# RPIBoard.net
KiCad netlist of a schematic drawn in EAGLE
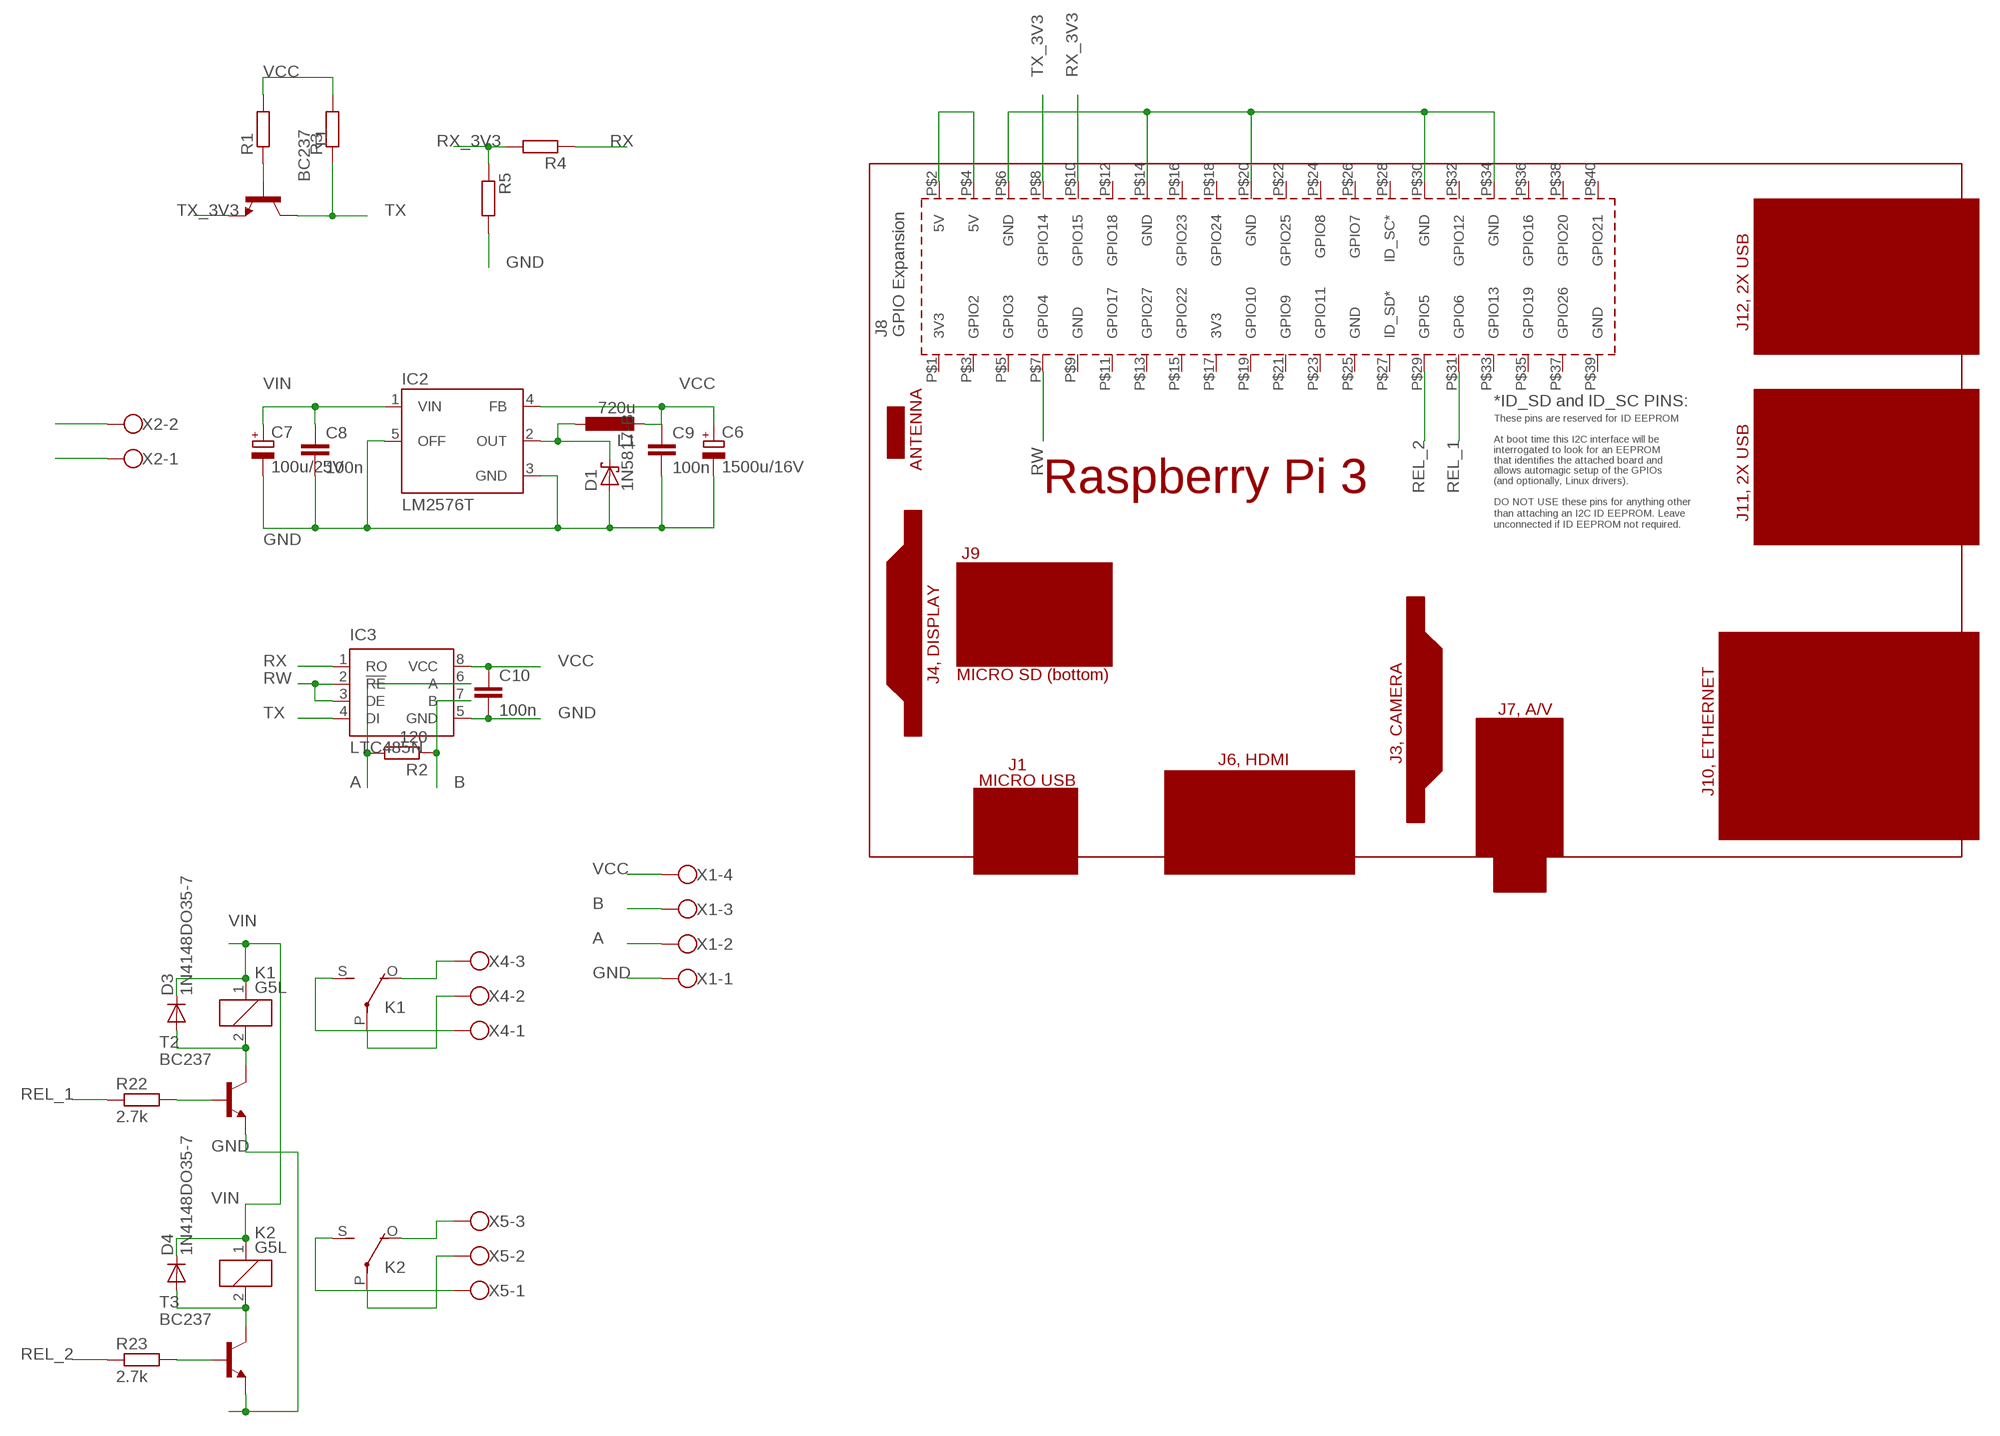
[diagram p0: schematic, sheet 1]

(export (version "E")
  (design (tool "Eeschema 10.0.6"))
  (components
    (comp (ref "C6")
      (value "1500u/16V")
      (footprint "eagle-import:E5-10,5")
      (libsource (lib "eagle-import") (part "CPOL-EUE5-10.5"))
    )
    (comp (ref "C7")
      (value "100u/25V")
      (footprint "eagle-import:E2,5-7")
      (libsource (lib "eagle-import") (part "CPOL-EUE2.5-7"))
    )
    (comp (ref "C8")
      (value "100n")
      (footprint "eagle-import:C025-024X044")
      (libsource (lib "eagle-import") (part "C-EU025-024X044"))
    )
    (comp (ref "C9")
      (value "100n")
      (footprint "eagle-import:C025-024X044")
      (libsource (lib "eagle-import") (part "C-EU025-024X044"))
    )
    (comp (ref "C10")
      (value "100n")
      (footprint "eagle-import:C025-024X044")
      (libsource (lib "eagle-import") (part "C-EU025-024X044"))
    )
    (comp (ref "D1")
      (value "1N5817-B")
      (footprint "eagle-import:DO41-7.6")
      (libsource (lib "eagle-import") (part "1N5817-B"))
    )
    (comp (ref "D3")
      (value "1N4148DO35-7")
      (footprint "eagle-import:DO35-7")
      (libsource (lib "eagle-import") (part "1N4148DO35-7"))
    )
    (comp (ref "D4")
      (value "1N4148DO35-7")
      (footprint "eagle-import:DO35-7")
      (libsource (lib "eagle-import") (part "1N4148DO35-7"))
    )
    (comp (ref "IC2")
      (value "LM2576T")
      (footprint "eagle-import:TO220-5")
      (libsource (lib "eagle-import") (part "LM2576T"))
    )
    (comp (ref "IC3")
      (value "LTC485N")
      (footprint "eagle-import:DIL08")
      (libsource (lib "eagle-import") (part "LTC485N"))
    )
    (comp (ref "K1")
      (value "G5L")
      (footprint "eagle-import:G5LE")
      (libsource (lib "eagle-import") (part "G5L"))
    )
    (comp (ref "K2")
      (value "G5L")
      (footprint "eagle-import:G5LE")
      (libsource (lib "eagle-import") (part "G5L"))
    )
    (comp (ref "L1")
      (value "720u")
      (footprint "eagle-import:TJ3-U1")
      (libsource (lib "eagle-import") (part "L-EUTJ3-U1"))
    )
    (comp (ref "PCB1")
      (value "RPI3")
      (footprint "eagle-import:RPI3")
      (libsource (lib "eagle-import") (part "RPI3"))
    )
    (comp (ref "R1")
      (value "R-EU_0207/7")
      (footprint "eagle-import:0207_7")
      (libsource (lib "eagle-import") (part "R-EU_0207/7"))
    )
    (comp (ref "R2")
      (value "120")
      (footprint "eagle-import:0204_7")
      (libsource (lib "eagle-import") (part "R-EU_0204/7"))
    )
    (comp (ref "R3")
      (value "R-EU_0207/7")
      (footprint "eagle-import:0207_7")
      (libsource (lib "eagle-import") (part "R-EU_0207/7"))
    )
    (comp (ref "R4")
      (value "R-EU_0207/7")
      (footprint "eagle-import:0207_7")
      (libsource (lib "eagle-import") (part "R-EU_0207/7"))
    )
    (comp (ref "R5")
      (value "R-EU_0207/7")
      (footprint "eagle-import:0207_7")
      (libsource (lib "eagle-import") (part "R-EU_0207/7"))
    )
    (comp (ref "R22")
      (value "2.7k")
      (footprint "eagle-import:0204_7")
      (libsource (lib "eagle-import") (part "R-EU_0204/7"))
    )
    (comp (ref "R23")
      (value "2.7k")
      (footprint "eagle-import:0204_7")
      (libsource (lib "eagle-import") (part "R-EU_0204/7"))
    )
    (comp (ref "T1")
      (value "BC237")
      (footprint "eagle-import:TO92")
      (libsource (lib "eagle-import") (part "BC237"))
    )
    (comp (ref "T2")
      (value "BC237")
      (footprint "eagle-import:TO92")
      (libsource (lib "eagle-import") (part "BC237"))
    )
    (comp (ref "T3")
      (value "BC237")
      (footprint "eagle-import:TO92")
      (libsource (lib "eagle-import") (part "BC237"))
    )
    (comp (ref "X1")
      (value "W237-4")
      (footprint "eagle-import:W237-4")
      (libsource (lib "eagle-import") (part "W237-4"))
    )
    (comp (ref "X2")
      (value "W237-102")
      (footprint "eagle-import:W237-102")
      (fields (field (name "MPN") "237-102"))
      (libsource (lib "eagle-import") (part "W237-102"))
    )
    (comp (ref "X4")
      (value "W237-103")
      (footprint "eagle-import:W237-103")
      (fields (field (name "MPN") "237-103"))
      (libsource (lib "eagle-import") (part "W237-103"))
    )
    (comp (ref "X5")
      (value "W237-103")
      (footprint "eagle-import:W237-103")
      (fields (field (name "MPN") "237-103"))
      (libsource (lib "eagle-import") (part "W237-103"))
    )
  )
  (nets
    (net (code "1") (name "/A") (class "Default")
      (node (ref "IC3") (pin "6") (pinfunction "A_6") (pintype "bidirectional"))
      (node (ref "R2") (pin "2") (pinfunction "2_2") (pintype "passive"))
      (node (ref "X1") (pin "2") (pinfunction "KL_2") (pintype "passive"))
    )
    (net (code "2") (name "/B") (class "Default")
      (node (ref "IC3") (pin "7") (pinfunction "B_7") (pintype "bidirectional"))
      (node (ref "R2") (pin "1") (pinfunction "1_1") (pintype "passive"))
      (node (ref "X1") (pin "3") (pinfunction "KL_3") (pintype "passive"))
    )
    (net (code "3") (name "/GND") (class "Default")
      (node (ref "C10") (pin "2") (pinfunction "2_2") (pintype "passive"))
      (node (ref "C6") (pin "-") (pinfunction "-_-") (pintype "passive"))
      (node (ref "C7") (pin "-") (pinfunction "-_-") (pintype "passive"))
      (node (ref "C8") (pin "2") (pinfunction "2_2") (pintype "passive"))
      (node (ref "C9") (pin "2") (pinfunction "2_2") (pintype "passive"))
      (node (ref "D1") (pin "A") (pinfunction "A_A") (pintype "passive"))
      (node (ref "IC2") (pin "3") (pinfunction "GND_3") (pintype "power_in"))
      (node (ref "IC2") (pin "5") (pinfunction "OFF_5") (pintype "input"))
      (node (ref "IC3") (pin "5") (pinfunction "GND_5") (pintype "input"))
      (node (ref "PCB1") (pin "P$14") (pinfunction "GND_P$14") (pintype "bidirectional"))
      (node (ref "PCB1") (pin "P$20") (pinfunction "GND_P$20") (pintype "bidirectional"))
      (node (ref "PCB1") (pin "P$30") (pinfunction "GND_P$30") (pintype "bidirectional"))
      (node (ref "PCB1") (pin "P$34") (pinfunction "GND_P$34") (pintype "bidirectional"))
      (node (ref "PCB1") (pin "P$6") (pinfunction "GND_P$6") (pintype "bidirectional"))
      (node (ref "R5") (pin "2") (pinfunction "2_2") (pintype "passive"))
      (node (ref "T2") (pin "1") (pinfunction "E_1") (pintype "passive"))
      (node (ref "T3") (pin "1") (pinfunction "E_1") (pintype "passive"))
      (node (ref "X1") (pin "1") (pinfunction "KL_1") (pintype "passive"))
      (node (ref "X2") (pin "1") (pinfunction "KL_1") (pintype "passive"))
    )
    (net (code "4") (name "/REL_1") (class "Default")
      (node (ref "PCB1") (pin "P$31") (pinfunction "GPIO6_P$31") (pintype "bidirectional"))
      (node (ref "R22") (pin "1") (pinfunction "1_1") (pintype "passive"))
    )
    (net (code "5") (name "/REL_2") (class "Default")
      (node (ref "PCB1") (pin "P$29") (pinfunction "GPIO5_P$29") (pintype "bidirectional"))
      (node (ref "R23") (pin "1") (pinfunction "1_1") (pintype "passive"))
    )
    (net (code "6") (name "/RW") (class "Default")
      (node (ref "IC3") (pin "2") (pinfunction "~{RE}_2") (pintype "input"))
      (node (ref "IC3") (pin "3") (pinfunction "DE_3") (pintype "input"))
      (node (ref "PCB1") (pin "P$7") (pinfunction "GPIO4_P$7") (pintype "bidirectional"))
    )
    (net (code "7") (name "/RX") (class "Default")
      (node (ref "IC3") (pin "1") (pinfunction "RO_1") (pintype "output"))
      (node (ref "R4") (pin "1") (pinfunction "1_1") (pintype "passive"))
    )
    (net (code "8") (name "/RX_3V3") (class "Default")
      (node (ref "PCB1") (pin "P$10") (pinfunction "GPIO15_P$10") (pintype "bidirectional"))
      (node (ref "R4") (pin "2") (pinfunction "2_2") (pintype "passive"))
      (node (ref "R5") (pin "1") (pinfunction "1_1") (pintype "passive"))
    )
    (net (code "9") (name "/TX") (class "Default")
      (node (ref "IC3") (pin "4") (pinfunction "DI_4") (pintype "input"))
      (node (ref "R3") (pin "1") (pinfunction "1_1") (pintype "passive"))
      (node (ref "T1") (pin "3") (pinfunction "C_3") (pintype "passive"))
    )
    (net (code "10") (name "/TX_3V3") (class "Default")
      (node (ref "PCB1") (pin "P$8") (pinfunction "GPIO14_P$8") (pintype "bidirectional"))
      (node (ref "T1") (pin "1") (pinfunction "E_1") (pintype "passive"))
    )
    (net (code "11") (name "/VCC") (class "Default")
      (node (ref "C10") (pin "1") (pinfunction "1_1") (pintype "passive"))
      (node (ref "C6") (pin "+") (pinfunction "+_+") (pintype "passive"))
      (node (ref "C9") (pin "1") (pinfunction "1_1") (pintype "passive"))
      (node (ref "IC2") (pin "4") (pinfunction "FB_4") (pintype "input"))
      (node (ref "IC3") (pin "8") (pinfunction "VCC_8") (pintype "input"))
      (node (ref "L1") (pin "2") (pinfunction "2_2") (pintype "passive"))
      (node (ref "PCB1") (pin "P$2") (pinfunction "5V_P$2") (pintype "bidirectional"))
      (node (ref "PCB1") (pin "P$4") (pinfunction "5V_P$4") (pintype "bidirectional"))
      (node (ref "R1") (pin "2") (pinfunction "2_2") (pintype "passive"))
      (node (ref "R3") (pin "2") (pinfunction "2_2") (pintype "passive"))
      (node (ref "X1") (pin "4") (pinfunction "KL_4") (pintype "passive"))
    )
    (net (code "12") (name "/VIN") (class "Default")
      (node (ref "C7") (pin "+") (pinfunction "+_+") (pintype "passive"))
      (node (ref "C8") (pin "1") (pinfunction "1_1") (pintype "passive"))
      (node (ref "D3") (pin "C") (pinfunction "C_C") (pintype "passive"))
      (node (ref "D4") (pin "C") (pinfunction "C_C") (pintype "passive"))
      (node (ref "IC2") (pin "1") (pinfunction "VIN_1") (pintype "power_in"))
      (node (ref "K1") (pin "1") (pinfunction "1_1") (pintype "passive"))
      (node (ref "K2") (pin "1") (pinfunction "1_1") (pintype "passive"))
      (node (ref "X2") (pin "2") (pinfunction "KL_2") (pintype "passive"))
    )
    (net (code "13") (name "Net-(IC2-OUT)") (class "Default")
      (node (ref "D1") (pin "C") (pinfunction "C_C") (pintype "passive"))
      (node (ref "IC2") (pin "2") (pinfunction "OUT_2") (pintype "output"))
      (node (ref "L1") (pin "1") (pinfunction "1_1") (pintype "passive"))
    )
    (net (code "14") (name "Net-(T1-B)") (class "Default")
      (node (ref "R1") (pin "1") (pinfunction "1_1") (pintype "passive"))
      (node (ref "T1") (pin "2") (pinfunction "B_2") (pintype "passive"))
    )
    (net (code "15") (name "Net-(T2-B)") (class "Default")
      (node (ref "R22") (pin "2") (pinfunction "2_2") (pintype "passive"))
      (node (ref "T2") (pin "2") (pinfunction "B_2") (pintype "passive"))
    )
    (net (code "16") (name "Net-(T2-C)") (class "Default")
      (node (ref "D3") (pin "A") (pinfunction "A_A") (pintype "passive"))
      (node (ref "K1") (pin "2") (pinfunction "2_2") (pintype "passive"))
      (node (ref "T2") (pin "3") (pinfunction "C_3") (pintype "passive"))
    )
    (net (code "17") (name "Net-(T3-B)") (class "Default")
      (node (ref "R23") (pin "2") (pinfunction "2_2") (pintype "passive"))
      (node (ref "T3") (pin "2") (pinfunction "B_2") (pintype "passive"))
    )
    (net (code "18") (name "Net-(T3-C)") (class "Default")
      (node (ref "D4") (pin "A") (pinfunction "A_A") (pintype "passive"))
      (node (ref "K2") (pin "2") (pinfunction "2_2") (pintype "passive"))
      (node (ref "T3") (pin "3") (pinfunction "C_3") (pintype "passive"))
    )
    (net (code "19") (name "Net-(X4A-KL)") (class "Default")
      (node (ref "K1") (pin "S") (pinfunction "S_S") (pintype "passive"))
      (node (ref "X4") (pin "1") (pinfunction "KL_1") (pintype "passive"))
    )
    (net (code "20") (name "Net-(X4B-KL)") (class "Default")
      (node (ref "K1") (pin "P") (pinfunction "P_P") (pintype "passive"))
      (node (ref "X4") (pin "2") (pinfunction "KL_2") (pintype "passive"))
    )
    (net (code "21") (name "Net-(X4C-KL)") (class "Default")
      (node (ref "K1") (pin "O") (pinfunction "O_O") (pintype "passive"))
      (node (ref "X4") (pin "3") (pinfunction "KL_3") (pintype "passive"))
    )
    (net (code "22") (name "Net-(X5A-KL)") (class "Default")
      (node (ref "K2") (pin "S") (pinfunction "S_S") (pintype "passive"))
      (node (ref "X5") (pin "1") (pinfunction "KL_1") (pintype "passive"))
    )
    (net (code "23") (name "Net-(X5B-KL)") (class "Default")
      (node (ref "K2") (pin "P") (pinfunction "P_P") (pintype "passive"))
      (node (ref "X5") (pin "2") (pinfunction "KL_2") (pintype "passive"))
    )
    (net (code "24") (name "Net-(X5C-KL)") (class "Default")
      (node (ref "K2") (pin "O") (pinfunction "O_O") (pintype "passive"))
      (node (ref "X5") (pin "3") (pinfunction "KL_3") (pintype "passive"))
    )
    (net (code "25") (name "unconnected-(PCB1-3V3-PadP$1)") (class "Default")
      (node (ref "PCB1") (pin "P$1") (pinfunction "3V3_P$1") (pintype "bidirectional"))
    )
    (net (code "26") (name "unconnected-(PCB1-3V3-PadP$17)") (class "Default")
      (node (ref "PCB1") (pin "P$17") (pinfunction "3V3_P$17") (pintype "bidirectional"))
    )
    (net (code "27") (name "unconnected-(PCB1-GND-PadP$9)") (class "Default")
      (node (ref "PCB1") (pin "P$9") (pinfunction "GND_P$9") (pintype "bidirectional"))
    )
    (net (code "28") (name "unconnected-(PCB1-GND-PadP$25)") (class "Default")
      (node (ref "PCB1") (pin "P$25") (pinfunction "GND_P$25") (pintype "bidirectional"))
    )
    (net (code "29") (name "unconnected-(PCB1-GND-PadP$39)") (class "Default")
      (node (ref "PCB1") (pin "P$39") (pinfunction "GND_P$39") (pintype "bidirectional"))
    )
    (net (code "30") (name "unconnected-(PCB1-GPIO2-PadP$3)") (class "Default")
      (node (ref "PCB1") (pin "P$3") (pinfunction "GPIO2_P$3") (pintype "bidirectional"))
    )
    (net (code "31") (name "unconnected-(PCB1-GPIO3-PadP$5)") (class "Default")
      (node (ref "PCB1") (pin "P$5") (pinfunction "GPIO3_P$5") (pintype "bidirectional"))
    )
    (net (code "32") (name "unconnected-(PCB1-GPIO7-PadP$26)") (class "Default")
      (node (ref "PCB1") (pin "P$26") (pinfunction "GPIO7_P$26") (pintype "bidirectional"))
    )
    (net (code "33") (name "unconnected-(PCB1-GPIO8-PadP$24)") (class "Default")
      (node (ref "PCB1") (pin "P$24") (pinfunction "GPIO8_P$24") (pintype "bidirectional"))
    )
    (net (code "34") (name "unconnected-(PCB1-GPIO9-PadP$21)") (class "Default")
      (node (ref "PCB1") (pin "P$21") (pinfunction "GPIO9_P$21") (pintype "bidirectional"))
    )
    (net (code "35") (name "unconnected-(PCB1-GPIO10-PadP$19)") (class "Default")
      (node (ref "PCB1") (pin "P$19") (pinfunction "GPIO10_P$19") (pintype "bidirectional"))
    )
    (net (code "36") (name "unconnected-(PCB1-GPIO11-PadP$23)") (class "Default")
      (node (ref "PCB1") (pin "P$23") (pinfunction "GPIO11_P$23") (pintype "bidirectional"))
    )
    (net (code "37") (name "unconnected-(PCB1-GPIO12-PadP$32)") (class "Default")
      (node (ref "PCB1") (pin "P$32") (pinfunction "GPIO12_P$32") (pintype "bidirectional"))
    )
    (net (code "38") (name "unconnected-(PCB1-GPIO13-PadP$33)") (class "Default")
      (node (ref "PCB1") (pin "P$33") (pinfunction "GPIO13_P$33") (pintype "bidirectional"))
    )
    (net (code "39") (name "unconnected-(PCB1-GPIO16-PadP$36)") (class "Default")
      (node (ref "PCB1") (pin "P$36") (pinfunction "GPIO16_P$36") (pintype "bidirectional"))
    )
    (net (code "40") (name "unconnected-(PCB1-GPIO17-PadP$11)") (class "Default")
      (node (ref "PCB1") (pin "P$11") (pinfunction "GPIO17_P$11") (pintype "bidirectional"))
    )
    (net (code "41") (name "unconnected-(PCB1-GPIO18-PadP$12)") (class "Default")
      (node (ref "PCB1") (pin "P$12") (pinfunction "GPIO18_P$12") (pintype "bidirectional"))
    )
    (net (code "42") (name "unconnected-(PCB1-GPIO19-PadP$35)") (class "Default")
      (node (ref "PCB1") (pin "P$35") (pinfunction "GPIO19_P$35") (pintype "bidirectional"))
    )
    (net (code "43") (name "unconnected-(PCB1-GPIO20-PadP$38)") (class "Default")
      (node (ref "PCB1") (pin "P$38") (pinfunction "GPIO20_P$38") (pintype "bidirectional"))
    )
    (net (code "44") (name "unconnected-(PCB1-GPIO21-PadP$40)") (class "Default")
      (node (ref "PCB1") (pin "P$40") (pinfunction "GPIO21_P$40") (pintype "bidirectional"))
    )
    (net (code "45") (name "unconnected-(PCB1-GPIO22-PadP$15)") (class "Default")
      (node (ref "PCB1") (pin "P$15") (pinfunction "GPIO22_P$15") (pintype "bidirectional"))
    )
    (net (code "46") (name "unconnected-(PCB1-GPIO23-PadP$16)") (class "Default")
      (node (ref "PCB1") (pin "P$16") (pinfunction "GPIO23_P$16") (pintype "bidirectional"))
    )
    (net (code "47") (name "unconnected-(PCB1-GPIO24-PadP$18)") (class "Default")
      (node (ref "PCB1") (pin "P$18") (pinfunction "GPIO24_P$18") (pintype "bidirectional"))
    )
    (net (code "48") (name "unconnected-(PCB1-GPIO25-PadP$22)") (class "Default")
      (node (ref "PCB1") (pin "P$22") (pinfunction "GPIO25_P$22") (pintype "bidirectional"))
    )
    (net (code "49") (name "unconnected-(PCB1-GPIO26-PadP$37)") (class "Default")
      (node (ref "PCB1") (pin "P$37") (pinfunction "GPIO26_P$37") (pintype "bidirectional"))
    )
    (net (code "50") (name "unconnected-(PCB1-GPIO27-PadP$13)") (class "Default")
      (node (ref "PCB1") (pin "P$13") (pinfunction "GPIO27_P$13") (pintype "bidirectional"))
    )
    (net (code "51") (name "unconnected-(PCB1-ID_SC*-PadP$28)") (class "Default")
      (node (ref "PCB1") (pin "P$28") (pinfunction "ID_SC*_P$28") (pintype "bidirectional"))
    )
    (net (code "52") (name "unconnected-(PCB1-ID_SD*-PadP$27)") (class "Default")
      (node (ref "PCB1") (pin "P$27") (pinfunction "ID_SD*_P$27") (pintype "bidirectional"))
    )
  )
)
